# AST1037.net
KiCad netlist of a schematic drawn in EAGLE
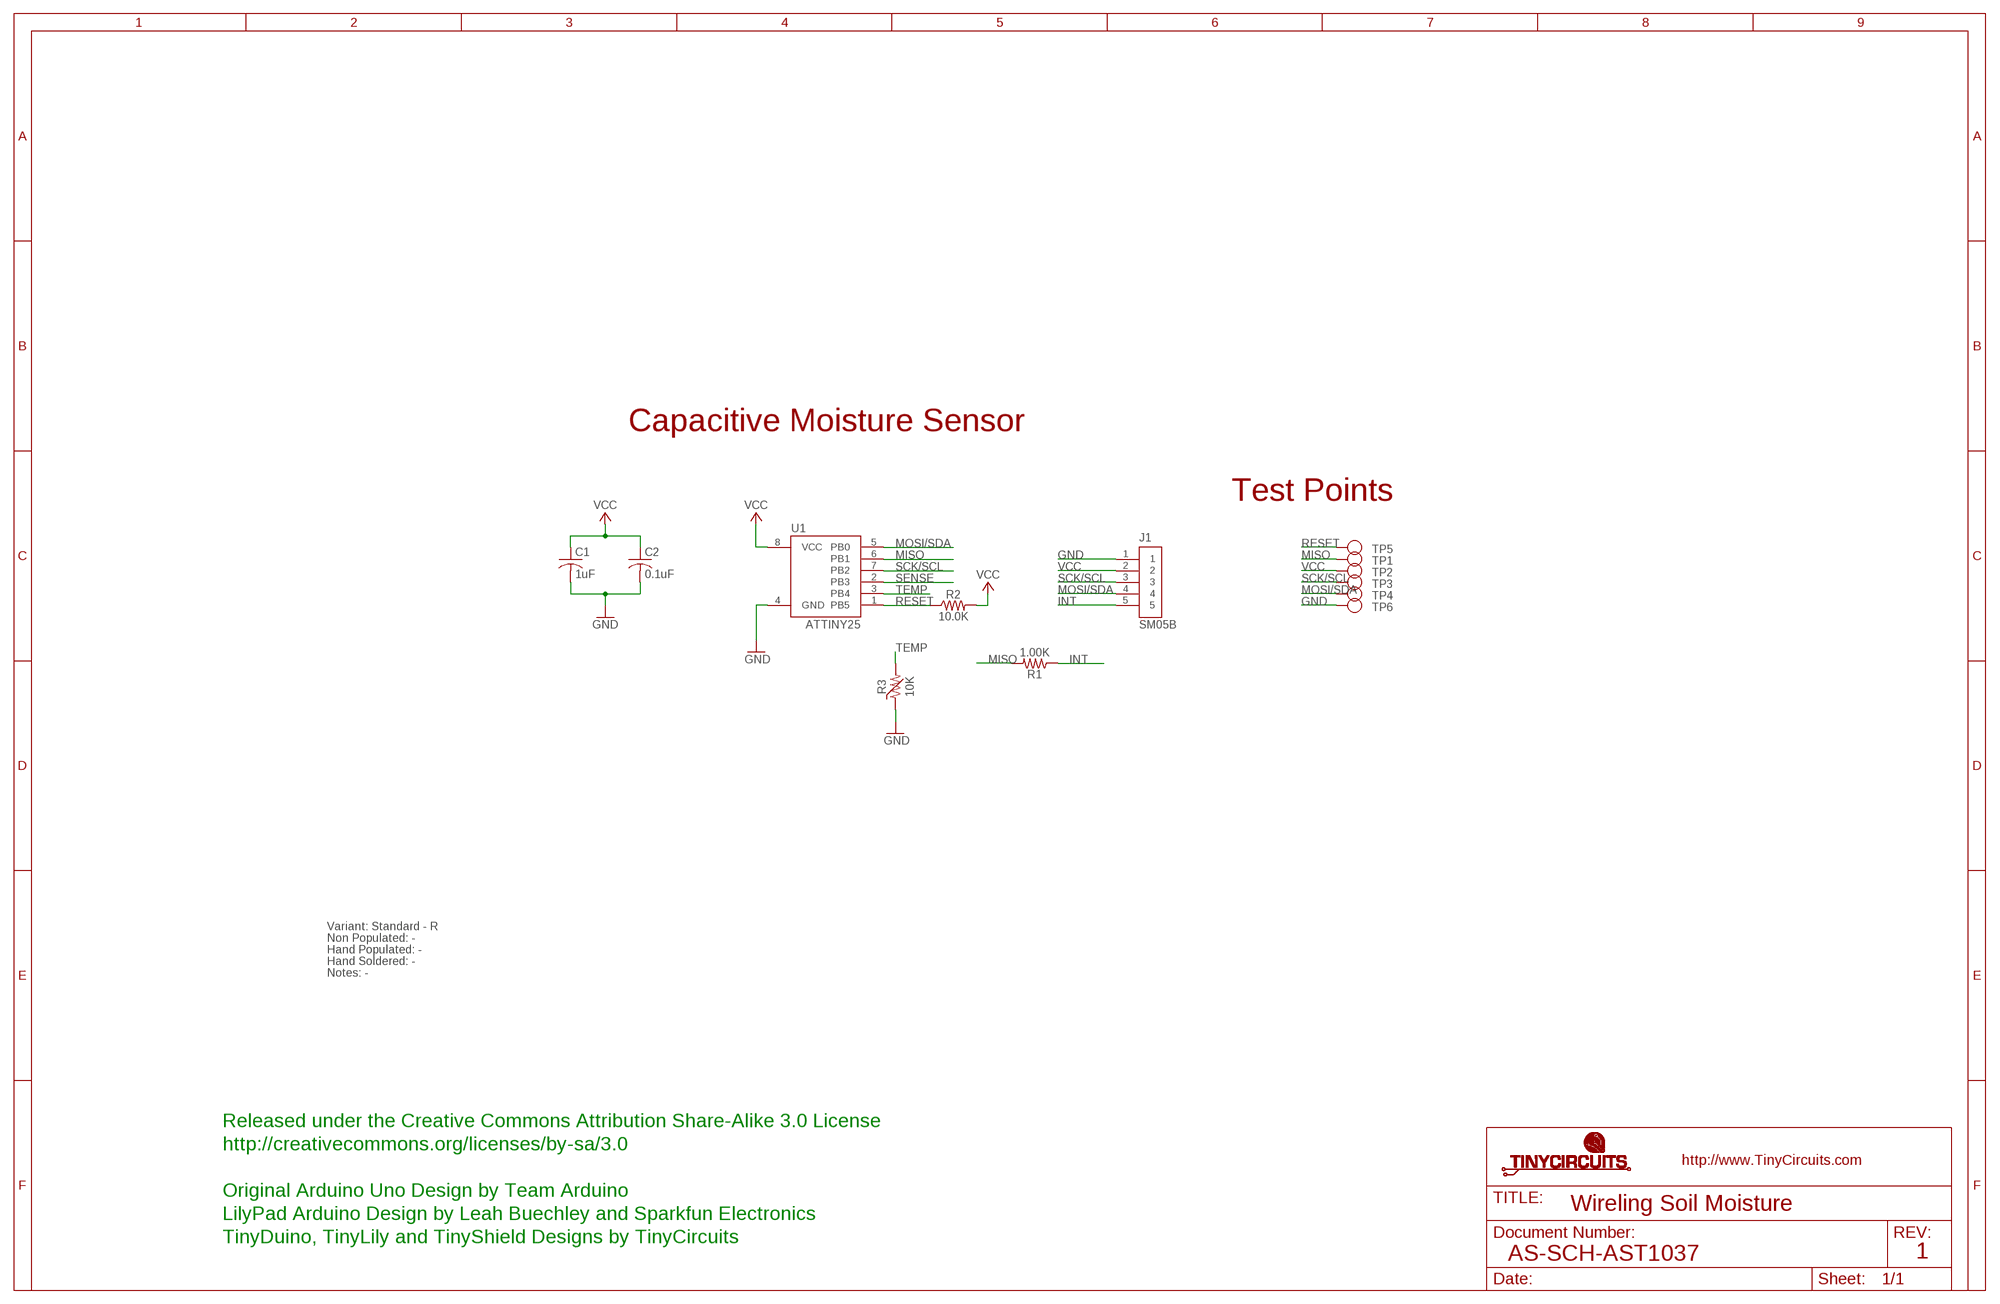
[diagram p0: schematic, sheet 1]

(export (version "E")
  (design (tool "Eeschema 10.0.6"))
  (components
    (comp (ref "C1")
      (value "1uF")
      (footprint "eagle-import:C0603")
      (fields (field (name "PARTNO") "AS-ITM-00410") (field (name "PARTNO_1") "AS-ITM-00410"))
      (libsource (lib "eagle-import") (part "AS-ITM-00410"))
    )
    (comp (ref "C2")
      (value "0.1uF")
      (footprint "eagle-import:C0402")
      (fields (field (name "PARTNO") "AS-ITM-00008"))
      (libsource (lib "eagle-import") (part "AS-ITM-00008"))
    )
    (comp (ref "J1")
      (value "SM05B")
      (footprint "eagle-import:JST_SH_5X1")
      (fields (field (name "PARTNO") "AS-ITM-00340"))
      (libsource (lib "eagle-import") (part "AS-ITM-00340"))
    )
    (comp (ref "R1")
      (value "1.00K")
      (footprint "eagle-import:0402")
      (fields (field (name "PARTNO") "AS-ITM-00003") (field (name "PARTNO_1") "AS-ITM-00003"))
      (libsource (lib "eagle-import") (part "AS-ITM-00003"))
    )
    (comp (ref "R2")
      (value "10.0K")
      (footprint "eagle-import:0402")
      (fields (field (name "PARTNO") "AS-ITM-00032"))
      (libsource (lib "eagle-import") (part "AS-ITM-00032"))
    )
    (comp (ref "R3")
      (value "10K")
      (footprint "eagle-import:0402")
      (fields (field (name "PARTNO") "AS-ITM-00524"))
      (libsource (lib "eagle-import") (part "AS-ITM-00524"))
    )
    (comp (ref "TP1")
      (value "TEST_POINT")
      (footprint "eagle-import:TEST_POINT_1MM")
      (libsource (lib "eagle-import") (part "TEST_POINT"))
    )
    (comp (ref "TP2")
      (value "TEST_POINT")
      (footprint "eagle-import:TEST_POINT_1MM")
      (libsource (lib "eagle-import") (part "TEST_POINT"))
    )
    (comp (ref "TP3")
      (value "TEST_POINT")
      (footprint "eagle-import:TEST_POINT_1MM")
      (libsource (lib "eagle-import") (part "TEST_POINT"))
    )
    (comp (ref "TP4")
      (value "TEST_POINT")
      (footprint "eagle-import:TEST_POINT_1MM")
      (libsource (lib "eagle-import") (part "TEST_POINT"))
    )
    (comp (ref "TP5")
      (value "TEST_POINT")
      (footprint "eagle-import:TEST_POINT_1MM")
      (libsource (lib "eagle-import") (part "TEST_POINT"))
    )
    (comp (ref "TP6")
      (value "TEST_POINT")
      (footprint "eagle-import:TEST_POINT_1MM")
      (libsource (lib "eagle-import") (part "TEST_POINT"))
    )
    (comp (ref "U1")
      (value "ATTINY25")
      (footprint "eagle-import:SO-08-COMPACT")
      (fields (field (name "PARTNO") "AS-ITM-00330"))
      (libsource (lib "eagle-import") (part "AS-ITM-00330"))
    )
  )
  (nets
    (net (code "1") (name "/INT") (class "Default")
      (node (ref "J1") (pin "5") (pinfunction "5_5") (pintype "bidirectional"))
      (node (ref "R1") (pin "1") (pinfunction "1_1") (pintype "passive"))
    )
    (net (code "2") (name "/MISO") (class "Default")
      (node (ref "R1") (pin "2") (pinfunction "2_2") (pintype "passive"))
      (node (ref "TP1") (pin "P$1") (pinfunction "1_P$1") (pintype "bidirectional"))
      (node (ref "U1") (pin "6") (pinfunction "PB1_6") (pintype "bidirectional"))
    )
    (net (code "3") (name "/MOSI{slash}SDA") (class "Default")
      (node (ref "J1") (pin "4") (pinfunction "4_4") (pintype "bidirectional"))
      (node (ref "TP4") (pin "P$1") (pinfunction "1_P$1") (pintype "bidirectional"))
      (node (ref "U1") (pin "5") (pinfunction "PB0_5") (pintype "bidirectional"))
    )
    (net (code "4") (name "/RESET") (class "Default")
      (node (ref "R2") (pin "1") (pinfunction "1_1") (pintype "passive"))
      (node (ref "TP5") (pin "P$1") (pinfunction "1_P$1") (pintype "bidirectional"))
      (node (ref "U1") (pin "1") (pinfunction "PB5_1") (pintype "bidirectional"))
    )
    (net (code "5") (name "/SCK{slash}SCL") (class "Default")
      (node (ref "J1") (pin "3") (pinfunction "3_3") (pintype "bidirectional"))
      (node (ref "TP3") (pin "P$1") (pinfunction "1_P$1") (pintype "bidirectional"))
      (node (ref "U1") (pin "7") (pinfunction "PB2_7") (pintype "bidirectional"))
    )
    (net (code "6") (name "/SENSE") (class "Default")
      (node (ref "U1") (pin "2") (pinfunction "PB3_2") (pintype "bidirectional"))
    )
    (net (code "7") (name "/TEMP") (class "Default")
      (node (ref "R3") (pin "2") (pinfunction "2_2") (pintype "passive"))
      (node (ref "U1") (pin "3") (pinfunction "PB4_3") (pintype "bidirectional"))
    )
    (net (code "8") (name "GND") (class "Default")
      (node (ref "C1") (pin "2") (pinfunction "2_2") (pintype "passive"))
      (node (ref "C2") (pin "2") (pinfunction "2_2") (pintype "passive"))
      (node (ref "J1") (pin "1") (pinfunction "1_1") (pintype "bidirectional"))
      (node (ref "R3") (pin "1") (pinfunction "1_1") (pintype "passive"))
      (node (ref "TP6") (pin "P$1") (pinfunction "1_P$1") (pintype "bidirectional"))
      (node (ref "U1") (pin "4") (pinfunction "GND_4") (pintype "bidirectional"))
    )
    (net (code "9") (name "VCC") (class "Default")
      (node (ref "C1") (pin "1") (pinfunction "1_1") (pintype "passive"))
      (node (ref "C2") (pin "1") (pinfunction "1_1") (pintype "passive"))
      (node (ref "J1") (pin "2") (pinfunction "2_2") (pintype "bidirectional"))
      (node (ref "R2") (pin "2") (pinfunction "2_2") (pintype "passive"))
      (node (ref "TP2") (pin "P$1") (pinfunction "1_P$1") (pintype "bidirectional"))
      (node (ref "U1") (pin "8") (pinfunction "VCC_8") (pintype "bidirectional"))
    )
  )
)
